# Sozu.net
KiCad netlist of a schematic drawn in EAGLE
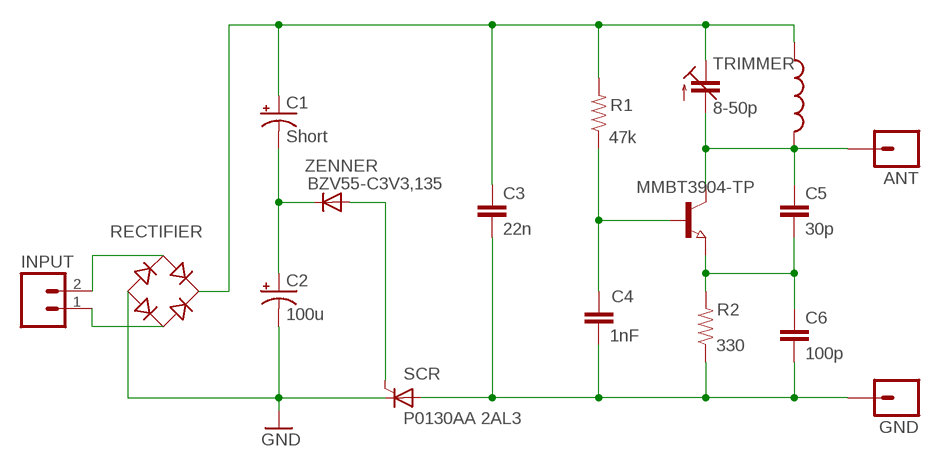
[diagram p0: schematic, sheet 1]

(export (version "E")
  (design (tool "Eeschema 10.0.6"))
  (components
    (comp (ref "ANT")
      (value "M01PTH")
      (footprint "eagle-import:1X01")
      (libsource (lib "eagle-import") (part "M01PTH"))
    )
    (comp (ref "C1")
      (value "Short")
      (footprint "eagle-import:ENERGY_CAP_2312")
      (libsource (lib "eagle-import") (part "ENERGY_CAP"))
    )
    (comp (ref "C2")
      (value "100u")
      (footprint "eagle-import:ENERGY_CAP_2312")
      (libsource (lib "eagle-import") (part "ENERGY_CAP"))
    )
    (comp (ref "C3")
      (value "22n")
      (footprint "eagle-import:0603-CAP")
      (libsource (lib "eagle-import") (part "CAP0603-CAP"))
    )
    (comp (ref "C4")
      (value "1nF")
      (footprint "eagle-import:0603-CAP")
      (libsource (lib "eagle-import") (part "CAP0603-CAP"))
    )
    (comp (ref "C5")
      (value "30p")
      (footprint "eagle-import:0603-CAP")
      (libsource (lib "eagle-import") (part "CAP0603-CAP"))
    )
    (comp (ref "C6")
      (value "100p")
      (footprint "eagle-import:0603-CAP")
      (libsource (lib "eagle-import") (part "CAP0603-CAP"))
    )
    (comp (ref "GND")
      (value "M01PTH")
      (footprint "eagle-import:1X01")
      (libsource (lib "eagle-import") (part "M01PTH"))
    )
    (comp (ref "INPUT")
      (value "M02PTH")
      (footprint "eagle-import:1X02")
      (libsource (lib "eagle-import") (part "M02PTH"))
    )
    (comp (ref "Q1")
      (value "MMBT3904-TP")
      (footprint "eagle-import:SOT23")
      (libsource (lib "eagle-import") (part "NPN-TRANSISTOR_SOT23"))
    )
    (comp (ref "R1")
      (value "47k")
      (footprint "eagle-import:0603-RES")
      (libsource (lib "eagle-import") (part "RESISTOR0603-RES"))
    )
    (comp (ref "R2")
      (value "330")
      (footprint "eagle-import:0603-RES")
      (libsource (lib "eagle-import") (part "RESISTOR0603-RES"))
    )
    (comp (ref "RECTIFIER")
      (value "SOZU_RECTIFIER")
      (footprint "eagle-import:RFTAG_RECTIFIER")
      (libsource (lib "eagle-import") (part "SOZU_RECTIFIER"))
    )
    (comp (ref "SCR")
      (value "P0130AA 2AL3")
      (footprint "eagle-import:TO92-2")
      (libsource (lib "eagle-import") (part "BT169"))
    )
    (comp (ref "TRIMMER")
      (value "8-50p")
      (footprint "eagle-import:SPARKFUN-CAPACITORS_GRM43D")
      (libsource (lib "eagle-import") (part "SOZU_TRIMMER_CAP"))
    )
    (comp (ref "U$2")
      (value "SOZU_INDUCTOR")
      (footprint "eagle-import:SOZU_INDUCTOR")
      (libsource (lib "eagle-import") (part "SOZU_INDUCTOR"))
    )
    (comp (ref "ZENNER")
      (value "BZV55-C3V3,135")
      (footprint "eagle-import:SOD-123")
      (libsource (lib "eagle-import") (part "DIODESOD-123"))
    )
  )
  (nets
    (net (code "1") (name "GND") (class "Default")
      (node (ref "C2") (pin "2") (pinfunction "-_2") (pintype "passive"))
      (node (ref "RECTIFIER") (pin "P$4") (pinfunction "-_P$4") (pintype "passive"))
      (node (ref "SCR") (pin "C") (pinfunction "C_C") (pintype "passive"))
    )
    (net (code "2") (name "Net-(C1-+)") (class "Default")
      (node (ref "C1") (pin "1") (pinfunction "+_1") (pintype "passive"))
      (node (ref "C3") (pin "1") (pinfunction "1_1") (pintype "passive"))
      (node (ref "R1") (pin "2") (pinfunction "2_2") (pintype "passive"))
      (node (ref "RECTIFIER") (pin "P$3") (pinfunction "+_P$3") (pintype "passive"))
      (node (ref "TRIMMER") (pin "C") (pinfunction "E_C") (pintype "passive"))
      (node (ref "U$2") (pin "1") (pinfunction "1_1") (pintype "passive"))
    )
    (net (code "3") (name "Net-(C1--)") (class "Default")
      (node (ref "C1") (pin "2") (pinfunction "-_2") (pintype "passive"))
      (node (ref "C2") (pin "1") (pinfunction "+_1") (pintype "passive"))
      (node (ref "ZENNER") (pin "C") (pinfunction "C_C") (pintype "passive"))
    )
    (net (code "4") (name "Net-(C3-Pad2)") (class "Default")
      (node (ref "C3") (pin "2") (pinfunction "2_2") (pintype "passive"))
      (node (ref "C4") (pin "2") (pinfunction "2_2") (pintype "passive"))
      (node (ref "C6") (pin "2") (pinfunction "2_2") (pintype "passive"))
      (node (ref "GND") (pin "1") (pinfunction "1_1") (pintype "passive"))
      (node (ref "R2") (pin "1") (pinfunction "1_1") (pintype "passive"))
      (node (ref "SCR") (pin "A") (pinfunction "A_A") (pintype "passive"))
    )
    (net (code "5") (name "Net-(Q1-B)") (class "Default")
      (node (ref "C4") (pin "1") (pinfunction "1_1") (pintype "passive"))
      (node (ref "Q1") (pin "1") (pinfunction "B_1") (pintype "passive"))
      (node (ref "R1") (pin "1") (pinfunction "1_1") (pintype "passive"))
    )
    (net (code "6") (name "Net-(Q1-C)") (class "Default")
      (node (ref "ANT") (pin "1") (pinfunction "1_1") (pintype "passive"))
      (node (ref "C5") (pin "1") (pinfunction "1_1") (pintype "passive"))
      (node (ref "Q1") (pin "3") (pinfunction "C_3") (pintype "passive"))
      (node (ref "TRIMMER") (pin "A") (pinfunction "A_A") (pintype "passive"))
      (node (ref "U$2") (pin "2") (pinfunction "2_2") (pintype "passive"))
    )
    (net (code "7") (name "Net-(Q1-E)") (class "Default")
      (node (ref "C5") (pin "2") (pinfunction "2_2") (pintype "passive"))
      (node (ref "C6") (pin "1") (pinfunction "1_1") (pintype "passive"))
      (node (ref "Q1") (pin "2") (pinfunction "E_2") (pintype "passive"))
      (node (ref "R2") (pin "2") (pinfunction "2_2") (pintype "passive"))
    )
    (net (code "8") (name "Net-(RECTIFIER-AC1)") (class "Default")
      (node (ref "INPUT") (pin "2") (pinfunction "2_2") (pintype "passive"))
      (node (ref "RECTIFIER") (pin "P$1") (pinfunction "AC1_P$1") (pintype "passive"))
    )
    (net (code "9") (name "Net-(RECTIFIER-AC2)") (class "Default")
      (node (ref "INPUT") (pin "1") (pinfunction "1_1") (pintype "passive"))
      (node (ref "RECTIFIER") (pin "P$2") (pinfunction "AC2_P$2") (pintype "passive"))
    )
    (net (code "10") (name "Net-(SCR-PadG)") (class "Default")
      (node (ref "SCR") (pin "G") (pinfunction "G_G") (pintype "passive"))
      (node (ref "ZENNER") (pin "A") (pinfunction "A_A") (pintype "passive"))
    )
  )
)
